# design.net
KiCad netlist of a schematic drawn in Altium Designer
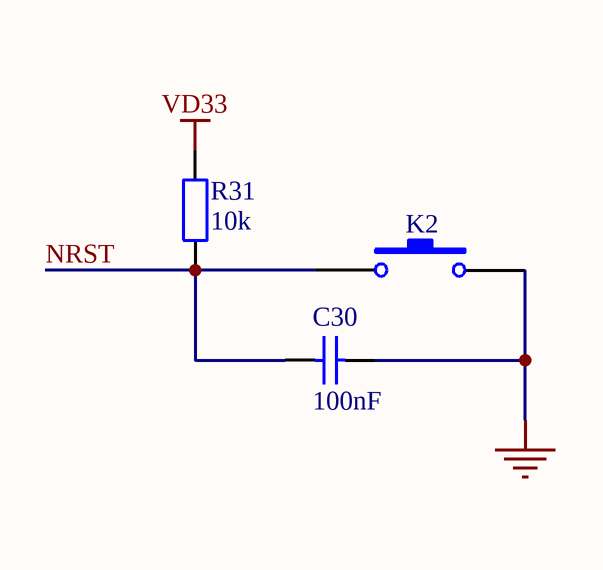
[diagram p0: 复位.SchDoc]

(export (version "E")
  (design (tool "Eeschema 10.0.6"))
  (components
    (comp (ref "C30")
      (value "100nF")
      (footprint "LC-0805_C")
      (description "100nF��0805��50V,+/-10%")
      (libsource (lib "ECG") (part "Cap"))
    )
    (comp (ref "K2")
      (value "�ᴥ����")
      (footprint "SW6X6")
      (description "�ᴥ����6��6mm,�Ľǲ��")
      (fields (field (name "PUBLISHER") "Altium Limited"))
      (libsource (lib "ECG") (part "SW-PB"))
    )
    (comp (ref "R31")
      (value "10k")
      (footprint "LC-0805_R")
      (description "10k��,0805,��5%")
      (libsource (lib "ECG") (part "R"))
    )
  )
  (nets
    (net (code "1") (name "/NRST") (class "Default")
      (node (ref "C30") (pin "1") (pinfunction "1_1") (pintype "passive"))
      (node (ref "K2") (pin "1") (pinfunction "1_1") (pintype "passive"))
      (node (ref "R31") (pin "1") (pintype "passive"))
    )
    (net (code "2") (name "<NO NET>") (class "Default")
      (node (ref "C30") (pin "2") (pinfunction "2_2") (pintype "passive"))
      (node (ref "K2") (pin "2") (pinfunction "2_2") (pintype "passive"))
    )
    (net (code "3") (name "VD33") (class "Default") (node (ref "R31") (pin "2") (pintype "passive")))
  )
)
